# BRX.net
KiCad netlist of a schematic drawn in EAGLE
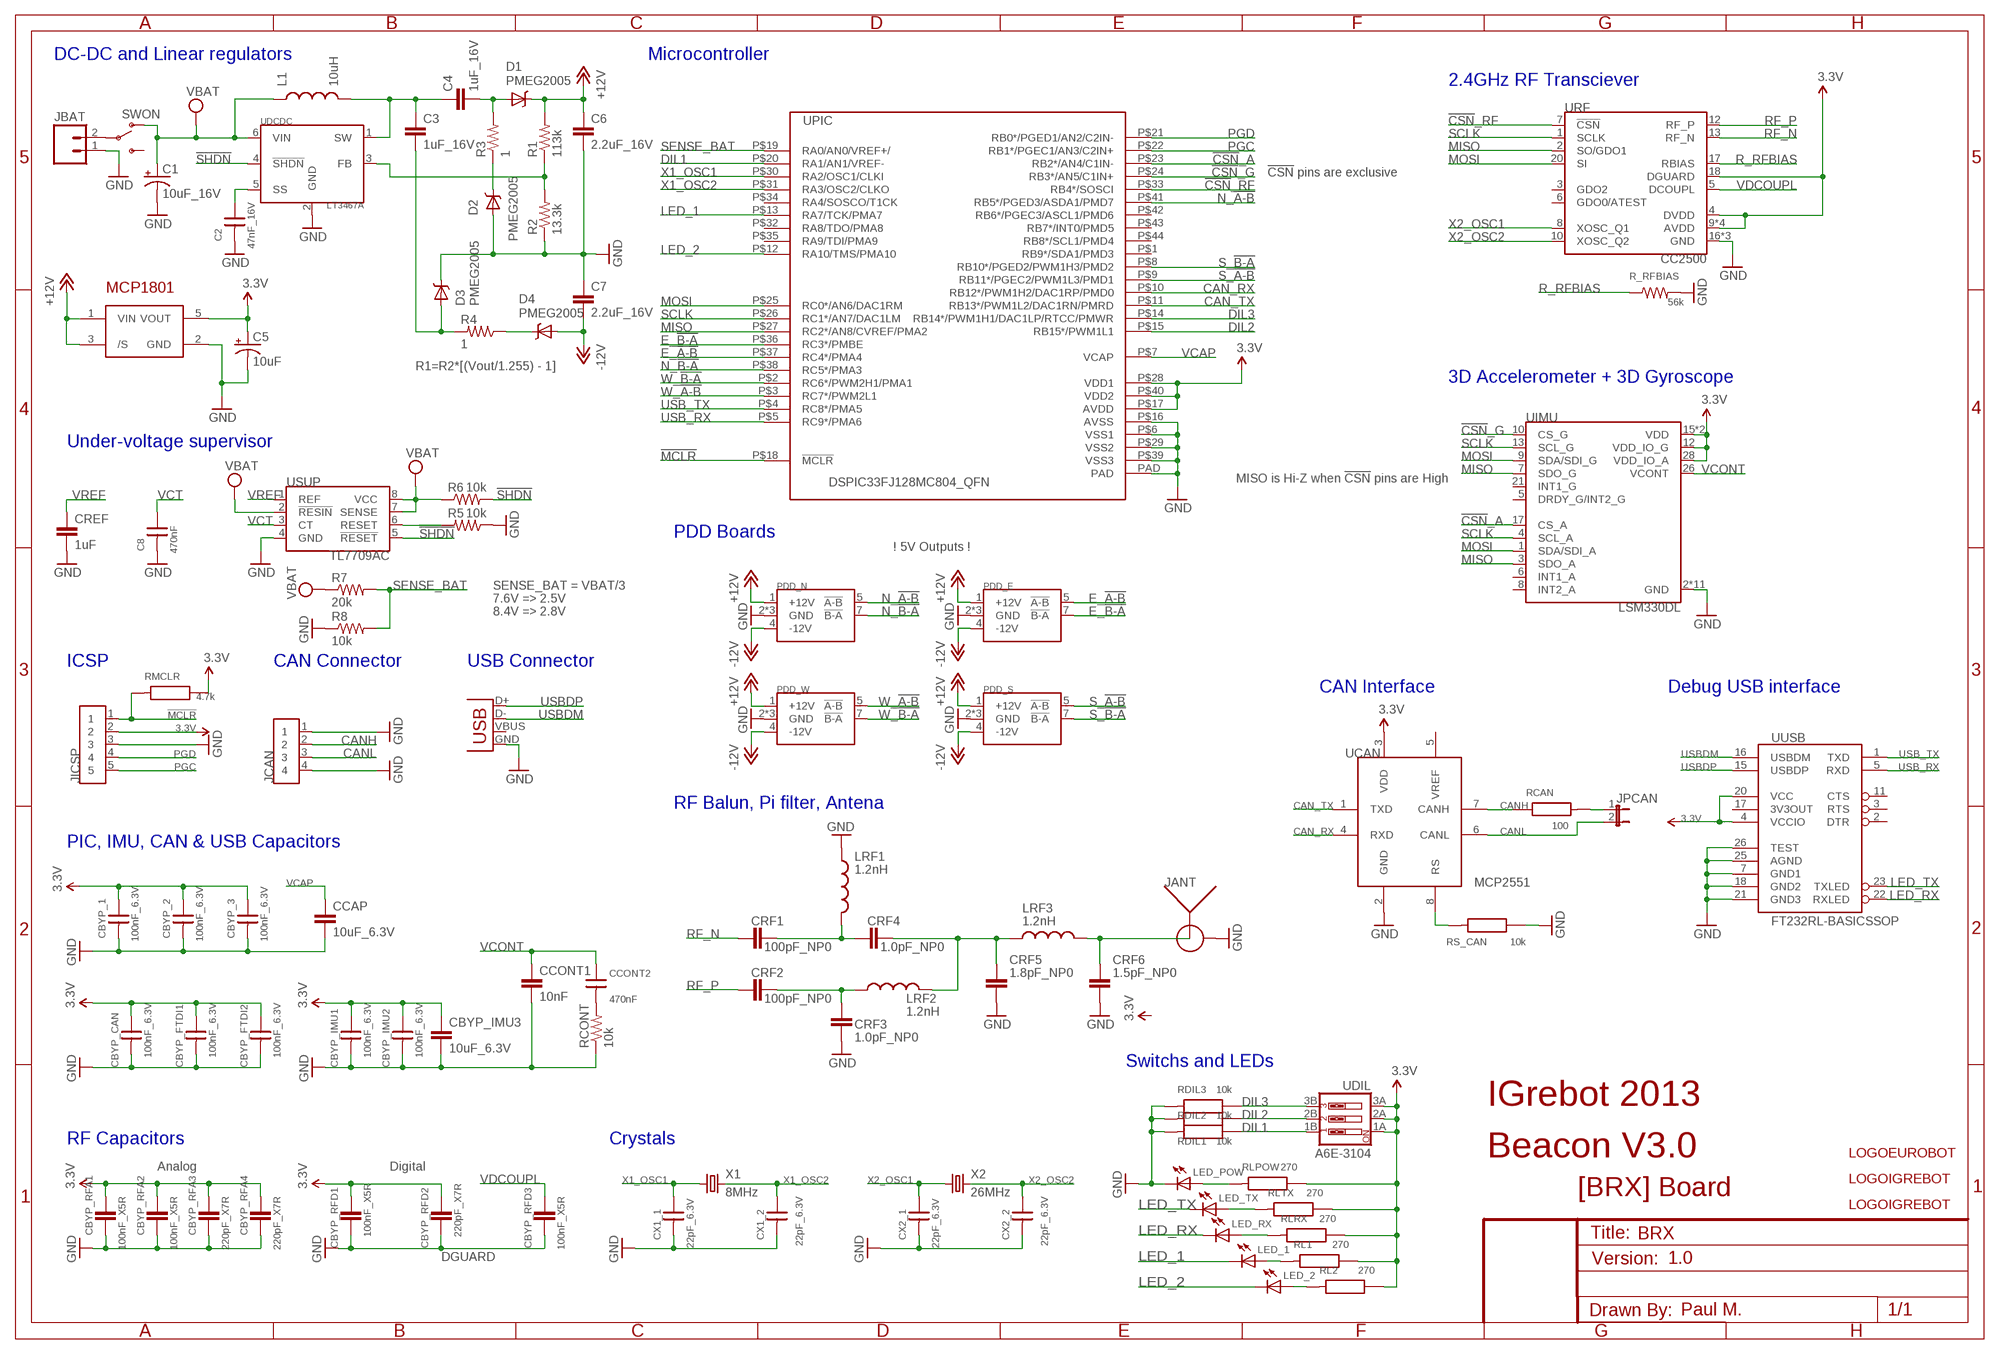
[diagram p0: schematic, sheet 1]

(export (version "E")
  (design (tool "Eeschema 10.0.6"))
  (components
    (comp (ref "C1")
      (value "10uF_16V")
      (footprint "eagle-import:PANASONIC_C")
      (libsource (lib "eagle-import") (part "CAP_POLC"))
    )
    (comp (ref "C2")
      (value "47nF_16V")
      (footprint "eagle-import:R0603")
      (libsource (lib "eagle-import") (part "C0603"))
    )
    (comp (ref "C3")
      (value "1uF_16V")
      (footprint "eagle-import:1210")
      (libsource (lib "eagle-import") (part "SparkFun-Passives_CAP1210"))
    )
    (comp (ref "C4")
      (value "1uF_16V")
      (footprint "eagle-import:1210")
      (libsource (lib "eagle-import") (part "SparkFun-Passives_CAP1210"))
    )
    (comp (ref "C5")
      (value "10uF")
      (footprint "eagle-import:PANASONIC_C")
      (libsource (lib "eagle-import") (part "CAP_POLC"))
    )
    (comp (ref "C6")
      (value "2.2uF_16V")
      (footprint "eagle-import:1210")
      (libsource (lib "eagle-import") (part "SparkFun-Passives_CAP1210"))
    )
    (comp (ref "C7")
      (value "2.2uF_16V")
      (footprint "eagle-import:1210")
      (libsource (lib "eagle-import") (part "SparkFun-Passives_CAP1210"))
    )
    (comp (ref "C8")
      (value "470nF")
      (footprint "eagle-import:R0603")
      (libsource (lib "eagle-import") (part "C0603"))
    )
    (comp (ref "CBYP_1")
      (value "100nF_6.3V")
      (footprint "eagle-import:R0603")
      (libsource (lib "eagle-import") (part "C0603"))
    )
    (comp (ref "CBYP_2")
      (value "100nF_6.3V")
      (footprint "eagle-import:R0603")
      (libsource (lib "eagle-import") (part "C0603"))
    )
    (comp (ref "CBYP_3")
      (value "100nF_6.3V")
      (footprint "eagle-import:R0603")
      (libsource (lib "eagle-import") (part "C0603"))
    )
    (comp (ref "CBYP_CAN")
      (value "100nF_6.3V")
      (footprint "eagle-import:R0603")
      (libsource (lib "eagle-import") (part "C0603"))
    )
    (comp (ref "CBYP_FTDI1")
      (value "100nF_6.3V")
      (footprint "eagle-import:R0603")
      (libsource (lib "eagle-import") (part "C0603"))
    )
    (comp (ref "CBYP_FTDI2")
      (value "100nF_6.3V")
      (footprint "eagle-import:R0603")
      (libsource (lib "eagle-import") (part "C0603"))
    )
    (comp (ref "CBYP_IMU1")
      (value "100nF_6.3V")
      (footprint "eagle-import:R0603")
      (libsource (lib "eagle-import") (part "C0603"))
    )
    (comp (ref "CBYP_IMU2")
      (value "100nF_6.3V")
      (footprint "eagle-import:R0603")
      (libsource (lib "eagle-import") (part "C0603"))
    )
    (comp (ref "CBYP_IMU3")
      (value "10uF_6.3V")
      (footprint "eagle-import:1206")
      (libsource (lib "eagle-import") (part "CAP1206"))
    )
    (comp (ref "CBYP_RFA1")
      (value "100nF_X5R")
      (footprint "eagle-import:0402-CAP")
      (libsource (lib "eagle-import") (part "SparkFun-Passives_CAP0402-CAP"))
    )
    (comp (ref "CBYP_RFA2")
      (value "100nF_X5R")
      (footprint "eagle-import:0402-CAP")
      (libsource (lib "eagle-import") (part "SparkFun-Passives_CAP0402-CAP"))
    )
    (comp (ref "CBYP_RFA3")
      (value "220pF_X7R")
      (footprint "eagle-import:0402-CAP")
      (libsource (lib "eagle-import") (part "SparkFun-Passives_CAP0402-CAP"))
    )
    (comp (ref "CBYP_RFA4")
      (value "220pF_X7R")
      (footprint "eagle-import:0402-CAP")
      (libsource (lib "eagle-import") (part "SparkFun-Passives_CAP0402-CAP"))
    )
    (comp (ref "CBYP_RFD1")
      (value "100nF_X5R")
      (footprint "eagle-import:0402-CAP")
      (libsource (lib "eagle-import") (part "SparkFun-Passives_CAP0402-CAP"))
    )
    (comp (ref "CBYP_RFD2")
      (value "220pF_X7R")
      (footprint "eagle-import:0402-CAP")
      (libsource (lib "eagle-import") (part "SparkFun-Passives_CAP0402-CAP"))
    )
    (comp (ref "CBYP_RFD3")
      (value "100nF_X5R")
      (footprint "eagle-import:0402-CAP")
      (libsource (lib "eagle-import") (part "SparkFun-Passives_CAP0402-CAP"))
    )
    (comp (ref "CCAP")
      (value "10uF_6.3V")
      (footprint "eagle-import:1206")
      (libsource (lib "eagle-import") (part "CAP1206"))
    )
    (comp (ref "CCONT1")
      (value "10nF")
      (footprint "eagle-import:1206")
      (libsource (lib "eagle-import") (part "CAP1206"))
    )
    (comp (ref "CCONT2")
      (value "470nF")
      (footprint "eagle-import:R0603")
      (libsource (lib "eagle-import") (part "C0603"))
    )
    (comp (ref "CREF")
      (value "1uF")
      (footprint "eagle-import:1210")
      (libsource (lib "eagle-import") (part "SparkFun-Passives_CAP1210"))
    )
    (comp (ref "CRF1")
      (value "100pF_NP0")
      (footprint "eagle-import:0402-CAP")
      (libsource (lib "eagle-import") (part "SparkFun-Passives_CAP0402-CAP"))
    )
    (comp (ref "CRF2")
      (value "100pF_NP0")
      (footprint "eagle-import:0402-CAP")
      (libsource (lib "eagle-import") (part "SparkFun-Passives_CAP0402-CAP"))
    )
    (comp (ref "CRF3")
      (value "1.0pF_NP0")
      (footprint "eagle-import:0402-CAP")
      (libsource (lib "eagle-import") (part "SparkFun-Passives_CAP0402-CAP"))
    )
    (comp (ref "CRF4")
      (value "1.0pF_NP0")
      (footprint "eagle-import:0402-CAP")
      (libsource (lib "eagle-import") (part "SparkFun-Passives_CAP0402-CAP"))
    )
    (comp (ref "CRF5")
      (value "1.8pF_NP0")
      (footprint "eagle-import:0402-CAP")
      (libsource (lib "eagle-import") (part "SparkFun-Passives_CAP0402-CAP"))
    )
    (comp (ref "CRF6")
      (value "1.5pF_NP0")
      (footprint "eagle-import:0402-CAP")
      (libsource (lib "eagle-import") (part "SparkFun-Passives_CAP0402-CAP"))
    )
    (comp (ref "CX1_1")
      (value "22pF_6.3V")
      (footprint "eagle-import:R0603")
      (libsource (lib "eagle-import") (part "C0603"))
    )
    (comp (ref "CX1_2")
      (value "22pF_6.3V")
      (footprint "eagle-import:R0603")
      (libsource (lib "eagle-import") (part "C0603"))
    )
    (comp (ref "CX2_1")
      (value "22pF_6.3V")
      (footprint "eagle-import:R0603")
      (libsource (lib "eagle-import") (part "C0603"))
    )
    (comp (ref "CX2_2")
      (value "22pF_6.3V")
      (footprint "eagle-import:R0603")
      (libsource (lib "eagle-import") (part "C0603"))
    )
    (comp (ref "D1")
      (value "PMEG2005")
      (footprint "eagle-import:SOD-523")
      (libsource (lib "eagle-import") (part "DIODE-SCHOTTKY"))
    )
    (comp (ref "D2")
      (value "PMEG2005")
      (footprint "eagle-import:SOD-523")
      (libsource (lib "eagle-import") (part "DIODE-SCHOTTKY"))
    )
    (comp (ref "D3")
      (value "PMEG2005")
      (footprint "eagle-import:SOD-523")
      (libsource (lib "eagle-import") (part "DIODE-SCHOTTKY"))
    )
    (comp (ref "D4")
      (value "PMEG2005")
      (footprint "eagle-import:SOD-523")
      (libsource (lib "eagle-import") (part "DIODE-SCHOTTKY"))
    )
    (comp (ref "JANT")
      (value "ENG_CD_1814400_C1")
      (footprint "eagle-import:SMA-PCB-ANGLE")
      (libsource (lib "eagle-import") (part "ENG_CD_1814400_C1"))
    )
    (comp (ref "JBAT")
      (value "M02JST-PTH-2")
      (footprint "eagle-import:JST-2-PTH")
      (libsource (lib "eagle-import") (part "M02JST-PTH-2"))
    )
    (comp (ref "JCAN")
      (value "SIL4")
      (footprint "eagle-import:CON4-2.54")
      (libsource (lib "eagle-import") (part "SIL4"))
    )
    (comp (ref "JICSP")
      (value "SIL5")
      (footprint "eagle-import:CON5-2.54")
      (libsource (lib "eagle-import") (part "SIL5"))
    )
    (comp (ref "JPCAN")
      (value "JUMPER-2PTH_LOCK")
      (footprint "eagle-import:1X02_LOCK")
      (libsource (lib "eagle-import") (part "JUMPER-2PTH_LOCK"))
    )
    (comp (ref "JUSB")
      (value "USBSMD")
      (footprint "eagle-import:USB-MINIB")
      (libsource (lib "eagle-import") (part "USBSMD"))
    )
    (comp (ref "L1")
      (value "10uH")
      (footprint "eagle-import:L-5X5")
      (libsource (lib "eagle-import") (part "MCSDC0503-221KU"))
    )
    (comp (ref "LED_1")
      (value "LED0603")
      (footprint "eagle-import:LED-0603")
      (libsource (lib "eagle-import") (part "LED0603"))
    )
    (comp (ref "LED_2")
      (value "LED0603")
      (footprint "eagle-import:LED-0603")
      (libsource (lib "eagle-import") (part "LED0603"))
    )
    (comp (ref "LED_POW")
      (value "LED0603")
      (footprint "eagle-import:LED-0603")
      (libsource (lib "eagle-import") (part "LED0603"))
    )
    (comp (ref "LED_RX")
      (value "LED0603")
      (footprint "eagle-import:LED-0603")
      (libsource (lib "eagle-import") (part "LED0603"))
    )
    (comp (ref "LED_TX")
      (value "LED0603")
      (footprint "eagle-import:LED-0603")
      (libsource (lib "eagle-import") (part "LED0603"))
    )
    (comp (ref "LRF1")
      (value "1.2nH")
      (footprint "eagle-import:C0402")
      (libsource (lib "eagle-import") (part "INDUCTOR0402"))
    )
    (comp (ref "LRF2")
      (value "1.2nH")
      (footprint "eagle-import:C0402")
      (libsource (lib "eagle-import") (part "INDUCTOR0402"))
    )
    (comp (ref "LRF3")
      (value "1.2nH")
      (footprint "eagle-import:C0402")
      (libsource (lib "eagle-import") (part "INDUCTOR0402"))
    )
    (comp (ref "PDD_E")
      (value "PDD_BOARD")
      (footprint "eagle-import:PDD_SOCKET")
      (libsource (lib "eagle-import") (part "PDD_BOARD"))
    )
    (comp (ref "PDD_N")
      (value "PDD_BOARD")
      (footprint "eagle-import:PDD_SOCKET")
      (libsource (lib "eagle-import") (part "PDD_BOARD"))
    )
    (comp (ref "PDD_S")
      (value "PDD_BOARD")
      (footprint "eagle-import:PDD_SOCKET")
      (libsource (lib "eagle-import") (part "PDD_BOARD"))
    )
    (comp (ref "PDD_W")
      (value "PDD_BOARD")
      (footprint "eagle-import:PDD_SOCKET")
      (libsource (lib "eagle-import") (part "PDD_BOARD"))
    )
    (comp (ref "R1")
      (value "113k")
      (footprint "eagle-import:0603-RES")
      (libsource (lib "eagle-import") (part "RESISTOR0603-RES"))
    )
    (comp (ref "R2")
      (value "13.3k")
      (footprint "eagle-import:0603-RES")
      (libsource (lib "eagle-import") (part "RESISTOR0603-RES"))
    )
    (comp (ref "R3")
      (value "1")
      (footprint "eagle-import:0603-RES")
      (libsource (lib "eagle-import") (part "RESISTOR0603-RES"))
    )
    (comp (ref "R4")
      (value "1")
      (footprint "eagle-import:0603-RES")
      (libsource (lib "eagle-import") (part "RESISTOR0603-RES"))
    )
    (comp (ref "R5")
      (value "10k")
      (footprint "eagle-import:0603-RES")
      (libsource (lib "eagle-import") (part "RESISTOR0603-RES"))
    )
    (comp (ref "R6")
      (value "10k")
      (footprint "eagle-import:0603-RES")
      (libsource (lib "eagle-import") (part "RESISTOR0603-RES"))
    )
    (comp (ref "R7")
      (value "20k")
      (footprint "eagle-import:0603-RES")
      (libsource (lib "eagle-import") (part "RESISTOR0603-RES"))
    )
    (comp (ref "R8")
      (value "10k")
      (footprint "eagle-import:0603-RES")
      (libsource (lib "eagle-import") (part "RESISTOR0603-RES"))
    )
    (comp (ref "RCAN")
      (value "100")
      (footprint "eagle-import:R0603")
      (libsource (lib "eagle-import") (part "R0603"))
    )
    (comp (ref "RCONT")
      (value "10k")
      (footprint "eagle-import:0603-RES")
      (libsource (lib "eagle-import") (part "RESISTOR0603-RES"))
    )
    (comp (ref "RDIL1")
      (value "10k")
      (footprint "eagle-import:R0603")
      (libsource (lib "eagle-import") (part "R0603"))
    )
    (comp (ref "RDIL2")
      (value "10k")
      (footprint "eagle-import:R0603")
      (libsource (lib "eagle-import") (part "R0603"))
    )
    (comp (ref "RDIL3")
      (value "10k")
      (footprint "eagle-import:R0603")
      (libsource (lib "eagle-import") (part "R0603"))
    )
    (comp (ref "RL1")
      (value "270")
      (footprint "eagle-import:R0603")
      (libsource (lib "eagle-import") (part "R0603"))
    )
    (comp (ref "RL2")
      (value "270")
      (footprint "eagle-import:R0603")
      (libsource (lib "eagle-import") (part "R0603"))
    )
    (comp (ref "RLPOW")
      (value "270")
      (footprint "eagle-import:R0603")
      (libsource (lib "eagle-import") (part "R0603"))
    )
    (comp (ref "RLRX")
      (value "270")
      (footprint "eagle-import:R0603")
      (libsource (lib "eagle-import") (part "R0603"))
    )
    (comp (ref "RLTX")
      (value "270")
      (footprint "eagle-import:R0603")
      (libsource (lib "eagle-import") (part "R0603"))
    )
    (comp (ref "RMCLR")
      (value "4.7k")
      (footprint "eagle-import:R0603")
      (libsource (lib "eagle-import") (part "R0603"))
    )
    (comp (ref "RS_CAN")
      (value "10k")
      (footprint "eagle-import:R0603")
      (libsource (lib "eagle-import") (part "R0603"))
    )
    (comp (ref "R_RFBIAS")
      (value "56k")
      (footprint "eagle-import:0402-RES")
      (libsource (lib "eagle-import") (part "RESISTOR0402-RES"))
    )
    (comp (ref "SWON")
      (value "SWITCH-SPDTPTH")
      (footprint "eagle-import:SWITCH-SPDT")
      (libsource (lib "eagle-import") (part "SWITCH-SPDTPTH"))
    )
    (comp (ref "U$3")
      (value "LOGOEUROBOT")
      (footprint "eagle-import:LOGO_EUROBOT_1")
      (libsource (lib "eagle-import") (part "LOGOEUROBOT"))
    )
    (comp (ref "U$5")
      (value "LOGOIGREBOT")
      (footprint "eagle-import:LOGO_IGREBOT")
      (libsource (lib "eagle-import") (part "LOGOIGREBOT"))
    )
    (comp (ref "U$9")
      (value "LOGOIGREBOT")
      (footprint "eagle-import:LOGO_IGREBOT")
      (libsource (lib "eagle-import") (part "LOGOIGREBOT"))
    )
    (comp (ref "UCAN")
      (value "MCP2551")
      (footprint "eagle-import:SO-08")
      (libsource (lib "eagle-import") (part "MCP2551"))
    )
    (comp (ref "UDCDC")
      (value "LT3467A")
      (footprint "eagle-import:TSOT-23")
      (libsource (lib "eagle-import") (part "LT3467A"))
    )
    (comp (ref "UDIL")
      (value "A6E-3104")
      (footprint "eagle-import:SW_DIP-3")
      (libsource (lib "eagle-import") (part "A6E-3104"))
    )
    (comp (ref "UIMU")
      (value "LSM330DL")
      (footprint "eagle-import:LLGA-28")
      (libsource (lib "eagle-import") (part "LSM330DL"))
    )
    (comp (ref "UPIC")
      (value "DSPIC33FJ128MC804_QFN")
      (footprint "eagle-import:QFN44-8X8")
      (libsource (lib "eagle-import") (part "DSPIC33FJ128MC804_QFN"))
    )
    (comp (ref "UREG")
      (value "MCP1801")
      (footprint "eagle-import:SOT23-5L")
      (libsource (lib "eagle-import") (part "MCP1801"))
    )
    (comp (ref "URF")
      (value "CC2500")
      (footprint "eagle-import:QFN20-0.5")
      (libsource (lib "eagle-import") (part "CC2500"))
    )
    (comp (ref "USUP")
      (value "TL7709AC")
      (footprint "eagle-import:SOIC8")
      (libsource (lib "eagle-import") (part "TL7709AC"))
    )
    (comp (ref "UUSB")
      (value "FT232RL-BASICSSOP")
      (footprint "eagle-import:SSOP28DB")
      (libsource (lib "eagle-import") (part "FT232RL-BASICSSOP"))
    )
    (comp (ref "X1")
      (value "8MHz")
      (footprint "eagle-import:XTAL_4.9-1.8")
      (libsource (lib "eagle-import") (part "XTAL4.8_1.8"))
    )
    (comp (ref "X2")
      (value "26MHz")
      (footprint "eagle-import:XTAL_4.9-1.8")
      (libsource (lib "eagle-import") (part "XTAL4.8_1.8"))
    )
  )
  (nets
    (net (code "1") (name "+12V") (class "Default")
      (node (ref "C6") (pin "1") (pinfunction "1_1") (pintype "passive"))
      (node (ref "D1") (pin "C") (pinfunction "C_C") (pintype "passive"))
      (node (ref "PDD_E") (pin "1") (pinfunction "+12V_1") (pintype "bidirectional"))
      (node (ref "PDD_N") (pin "1") (pinfunction "+12V_1") (pintype "bidirectional"))
      (node (ref "PDD_S") (pin "1") (pinfunction "+12V_1") (pintype "bidirectional"))
      (node (ref "PDD_W") (pin "1") (pinfunction "+12V_1") (pintype "bidirectional"))
      (node (ref "R1") (pin "2") (pinfunction "2_2") (pintype "passive"))
      (node (ref "UREG") (pin "1") (pinfunction "VIN_1") (pintype "bidirectional"))
      (node (ref "UREG") (pin "3") (pinfunction "/S_3") (pintype "bidirectional"))
    )
    (net (code "2") (name "-12V") (class "Default")
      (node (ref "C7") (pin "1") (pinfunction "1_1") (pintype "passive"))
      (node (ref "D4") (pin "A") (pinfunction "A_A") (pintype "passive"))
      (node (ref "PDD_E") (pin "4") (pinfunction "-12V_4") (pintype "bidirectional"))
      (node (ref "PDD_N") (pin "4") (pinfunction "-12V_4") (pintype "bidirectional"))
      (node (ref "PDD_S") (pin "4") (pinfunction "-12V_4") (pintype "bidirectional"))
      (node (ref "PDD_W") (pin "4") (pinfunction "-12V_4") (pintype "bidirectional"))
    )
    (net (code "3") (name "/CANH") (class "Default")
      (node (ref "JCAN") (pin "2") (pinfunction "2_2") (pintype "bidirectional"))
      (node (ref "RCAN") (pin "1") (pinfunction "1_1") (pintype "bidirectional"))
      (node (ref "UCAN") (pin "7") (pinfunction "CANH_7") (pintype "bidirectional"))
    )
    (net (code "4") (name "/CANL") (class "Default")
      (node (ref "JCAN") (pin "3") (pinfunction "3_3") (pintype "bidirectional"))
      (node (ref "JPCAN") (pin "2") (pinfunction "2_2") (pintype "passive"))
      (node (ref "UCAN") (pin "6") (pinfunction "CANL_6") (pintype "bidirectional"))
    )
    (net (code "5") (name "/CAN_RX") (class "Default")
      (node (ref "UCAN") (pin "4") (pinfunction "RXD_4") (pintype "bidirectional"))
      (node (ref "UPIC") (pin "P$10") (pinfunction "RB12*/PWM1H2/DAC1RP/PMD0_P$10") (pintype "bidirectional"))
    )
    (net (code "6") (name "/CAN_TX") (class "Default")
      (node (ref "UCAN") (pin "1") (pinfunction "TXD_1") (pintype "bidirectional"))
      (node (ref "UPIC") (pin "P$11") (pinfunction "RB13*/PWM1L2/DAC1RN/PMRD_P$11") (pintype "bidirectional"))
    )
    (net (code "7") (name "/DIL1") (class "Default")
      (node (ref "RDIL1") (pin "1") (pinfunction "1_1") (pintype "bidirectional"))
      (node (ref "UDIL") (pin "1B") (pinfunction "1B_1B") (pintype "passive"))
      (node (ref "UPIC") (pin "P$20") (pinfunction "RA1/AN1/VREF-_P$20") (pintype "bidirectional"))
    )
    (net (code "8") (name "/DIL2") (class "Default")
      (node (ref "RDIL2") (pin "1") (pinfunction "1_1") (pintype "bidirectional"))
      (node (ref "UDIL") (pin "2B") (pinfunction "2B_2B") (pintype "passive"))
      (node (ref "UPIC") (pin "P$15") (pinfunction "RB15*/PWM1L1_P$15") (pintype "bidirectional"))
    )
    (net (code "9") (name "/DIL3") (class "Default")
      (node (ref "RDIL3") (pin "1") (pinfunction "1_1") (pintype "bidirectional"))
      (node (ref "UDIL") (pin "3B") (pinfunction "3B_3B") (pintype "passive"))
      (node (ref "UPIC") (pin "P$14") (pinfunction "RB14*/PWM1H1/DAC1LP/RTCC/PMWR_P$14") (pintype "bidirectional"))
    )
    (net (code "10") (name "/E_~{A-B}") (class "Default")
      (node (ref "PDD_E") (pin "5") (pinfunction "~{A-B}_5") (pintype "bidirectional"))
      (node (ref "UPIC") (pin "P$37") (pinfunction "RC4*/PMA4_P$37") (pintype "bidirectional"))
    )
    (net (code "11") (name "/E_~{B-A}") (class "Default")
      (node (ref "PDD_E") (pin "7") (pinfunction "~{B-A}_7") (pintype "bidirectional"))
      (node (ref "UPIC") (pin "P$36") (pinfunction "RC3*/PMBE_P$36") (pintype "bidirectional"))
    )
    (net (code "12") (name "/LED_1") (class "Default")
      (node (ref "LED_1") (pin "C") (pinfunction "C_C") (pintype "passive"))
      (node (ref "UPIC") (pin "P$13") (pinfunction "RA7/TCK/PMA7_P$13") (pintype "bidirectional"))
    )
    (net (code "13") (name "/LED_2") (class "Default")
      (node (ref "LED_2") (pin "C") (pinfunction "C_C") (pintype "passive"))
      (node (ref "UPIC") (pin "P$12") (pinfunction "RA10/TMS/PMA10_P$12") (pintype "bidirectional"))
    )
    (net (code "14") (name "/LED_RX") (class "Default")
      (node (ref "LED_RX") (pin "C") (pinfunction "C_C") (pintype "passive"))
      (node (ref "UUSB") (pin "22") (pinfunction "RXLED_22") (pintype "bidirectional"))
    )
    (net (code "15") (name "/LED_TX") (class "Default")
      (node (ref "LED_TX") (pin "C") (pinfunction "C_C") (pintype "passive"))
      (node (ref "UUSB") (pin "23") (pinfunction "TXLED_23") (pintype "bidirectional"))
    )
    (net (code "16") (name "/MISO") (class "Default")
      (node (ref "UIMU") (pin "3") (pinfunction "SDO_A_3") (pintype "bidirectional"))
      (node (ref "UIMU") (pin "7") (pinfunction "SDO_G_7") (pintype "bidirectional"))
      (node (ref "UPIC") (pin "P$27") (pinfunction "RC2*/AN8/CVREF/PMA2_P$27") (pintype "bidirectional"))
      (node (ref "URF") (pin "2") (pinfunction "SO/GDO1_2") (pintype "bidirectional"))
    )
    (net (code "17") (name "/MOSI") (class "Default")
      (node (ref "UIMU") (pin "1") (pinfunction "SDA/SDI_A_1") (pintype "bidirectional"))
      (node (ref "UIMU") (pin "9") (pinfunction "SDA/SDI_G_9") (pintype "bidirectional"))
      (node (ref "UPIC") (pin "P$25") (pinfunction "RC0*/AN6/DAC1RM_P$25") (pintype "bidirectional"))
      (node (ref "URF") (pin "20") (pinfunction "SI_20") (pintype "bidirectional"))
    )
    (net (code "18") (name "/N_~{A-B}") (class "Default")
      (node (ref "PDD_N") (pin "5") (pinfunction "~{A-B}_5") (pintype "bidirectional"))
      (node (ref "UPIC") (pin "P$41") (pinfunction "RB5*/PGED3/ASDA1/PMD7_P$41") (pintype "bidirectional"))
    )
    (net (code "19") (name "/N_~{B-A}") (class "Default")
      (node (ref "PDD_N") (pin "7") (pinfunction "~{B-A}_7") (pintype "bidirectional"))
      (node (ref "UPIC") (pin "P$38") (pinfunction "RC5*/PMA3_P$38") (pintype "bidirectional"))
    )
    (net (code "20") (name "/PGC") (class "Default")
      (node (ref "JICSP") (pin "5") (pinfunction "5_5") (pintype "bidirectional"))
      (node (ref "UPIC") (pin "P$22") (pinfunction "RB1*/PGEC1/AN3/C2IN+_P$22") (pintype "bidirectional"))
    )
    (net (code "21") (name "/PGD") (class "Default")
      (node (ref "JICSP") (pin "4") (pinfunction "4_4") (pintype "bidirectional"))
      (node (ref "UPIC") (pin "P$21") (pinfunction "RB0*/PGED1/AN2/C2IN-_P$21") (pintype "bidirectional"))
    )
    (net (code "22") (name "/RF_N") (class "Default")
      (node (ref "CRF1") (pin "1") (pinfunction "1_1") (pintype "passive"))
      (node (ref "URF") (pin "13") (pinfunction "RF_N_13") (pintype "bidirectional"))
    )
    (net (code "23") (name "/RF_P") (class "Default")
      (node (ref "CRF2") (pin "1") (pinfunction "1_1") (pintype "passive"))
      (node (ref "URF") (pin "12") (pinfunction "RF_P_12") (pintype "bidirectional"))
    )
    (net (code "24") (name "/R_RFBIAS") (class "Default")
      (node (ref "R_RFBIAS") (pin "1") (pinfunction "1_1") (pintype "passive"))
      (node (ref "URF") (pin "17") (pinfunction "RBIAS_17") (pintype "bidirectional"))
    )
    (net (code "25") (name "/SCLK") (class "Default")
      (node (ref "UIMU") (pin "13") (pinfunction "SCL_G_13") (pintype "bidirectional"))
      (node (ref "UIMU") (pin "4") (pinfunction "SCL_A_4") (pintype "bidirectional"))
      (node (ref "UPIC") (pin "P$26") (pinfunction "RC1*/AN7/DAC1LM_P$26") (pintype "bidirectional"))
      (node (ref "URF") (pin "1") (pinfunction "SCLK_1") (pintype "bidirectional"))
    )
    (net (code "26") (name "/SENSE_BAT") (class "Default")
      (node (ref "R7") (pin "2") (pinfunction "2_2") (pintype "passive"))
      (node (ref "R8") (pin "2") (pinfunction "2_2") (pintype "passive"))
      (node (ref "UPIC") (pin "P$19") (pinfunction "RA0/AN0/VREF+/_P$19") (pintype "bidirectional"))
    )
    (net (code "27") (name "/S_~{A-B}") (class "Default")
      (node (ref "PDD_S") (pin "5") (pinfunction "~{A-B}_5") (pintype "bidirectional"))
      (node (ref "UPIC") (pin "P$9") (pinfunction "RB11*/PGEC2/PWM1L3/PMD1_P$9") (pintype "bidirectional"))
    )
    (net (code "28") (name "/S_~{B-A}") (class "Default")
      (node (ref "PDD_S") (pin "7") (pinfunction "~{B-A}_7") (pintype "bidirectional"))
      (node (ref "UPIC") (pin "P$8") (pinfunction "RB10*/PGED2/PWM1H3/PMD2_P$8") (pintype "bidirectional"))
    )
    (net (code "29") (name "/USBDM") (class "Default")
      (node (ref "JUSB") (pin "D-") (pinfunction "D-_D-") (pintype "bidirectional"))
      (node (ref "UUSB") (pin "16") (pinfunction "USBDM_16") (pintype "bidirectional"))
    )
    (net (code "30") (name "/USBDP") (class "Default")
      (node (ref "JUSB") (pin "D+") (pinfunction "D+_D+") (pintype "bidirectional"))
      (node (ref "UUSB") (pin "15") (pinfunction "USBDP_15") (pintype "bidirectional"))
    )
    (net (code "31") (name "/USB_RX") (class "Default")
      (node (ref "UPIC") (pin "P$5") (pinfunction "RC9*/PMA6_P$5") (pintype "bidirectional"))
      (node (ref "UUSB") (pin "5") (pinfunction "RXD_5") (pintype "input"))
    )
    (net (code "32") (name "/USB_TX") (class "Default")
      (node (ref "UPIC") (pin "P$4") (pinfunction "RC8*/PMA5_P$4") (pintype "bidirectional"))
      (node (ref "UUSB") (pin "1") (pinfunction "TXD_1") (pintype "output"))
    )
    (net (code "33") (name "/VCAP") (class "Default")
      (node (ref "CCAP") (pin "1") (pinfunction "1_1") (pintype "passive"))
      (node (ref "UPIC") (pin "P$7") (pinfunction "VCAP_P$7") (pintype "bidirectional"))
    )
    (net (code "34") (name "/VCONT") (class "Default")
      (node (ref "CCONT1") (pin "1") (pinfunction "1_1") (pintype "passive"))
      (node (ref "CCONT2") (pin "1") (pinfunction "1_1") (pintype "bidirectional"))
      (node (ref "UIMU") (pin "26") (pinfunction "VCONT_26") (pintype "bidirectional"))
    )
    (net (code "35") (name "/VCT") (class "Default")
      (node (ref "C8") (pin "1") (pinfunction "1_1") (pintype "bidirectional"))
      (node (ref "USUP") (pin "3") (pinfunction "CT_3") (pintype "bidirectional"))
    )
    (net (code "36") (name "/VDCOUPL") (class "Default")
      (node (ref "CBYP_RFD3") (pin "2") (pinfunction "2_2") (pintype "passive"))
      (node (ref "URF") (pin "5") (pinfunction "DCOUPL_5") (pintype "bidirectional"))
    )
    (net (code "37") (name "/VREF") (class "Default")
      (node (ref "CREF") (pin "2") (pinfunction "2_2") (pintype "passive"))
      (node (ref "USUP") (pin "1") (pinfunction "REF_1") (pintype "bidirectional"))
    )
    (net (code "38") (name "/W_~{A-B}") (class "Default")
      (node (ref "PDD_W") (pin "5") (pinfunction "~{A-B}_5") (pintype "bidirectional"))
      (node (ref "UPIC") (pin "P$3") (pinfunction "RC7*/PWM2L1_P$3") (pintype "bidirectional"))
    )
    (net (code "39") (name "/W_~{B-A}") (class "Default")
      (node (ref "PDD_W") (pin "7") (pinfunction "~{B-A}_7") (pintype "bidirectional"))
      (node (ref "UPIC") (pin "P$2") (pinfunction "RC6*/PWM2H1/PMA1_P$2") (pintype "bidirectional"))
    )
    (net (code "40") (name "/X1_OSC1") (class "Default")
      (node (ref "CX1_1") (pin "1") (pinfunction "1_1") (pintype "bidirectional"))
      (node (ref "UPIC") (pin "P$30") (pinfunction "RA2/OSC1/CLKI_P$30") (pintype "bidirectional"))
      (node (ref "X1") (pin "P$1") (pinfunction "1_P$1") (pintype "passive"))
    )
    (net (code "41") (name "/X1_OSC2") (class "Default")
      (node (ref "CX1_2") (pin "1") (pinfunction "1_1") (pintype "bidirectional"))
      (node (ref "UPIC") (pin "P$31") (pinfunction "RA3/OSC2/CLKO_P$31") (pintype "bidirectional"))
      (node (ref "X1") (pin "P$2") (pinfunction "2_P$2") (pintype "passive"))
    )
    (net (code "42") (name "/X2_OSC1") (class "Default")
      (node (ref "CX2_1") (pin "1") (pinfunction "1_1") (pintype "bidirectional"))
      (node (ref "URF") (pin "8") (pinfunction "XOSC_Q1_8") (pintype "bidirectional"))
      (node (ref "X2") (pin "P$1") (pinfunction "1_P$1") (pintype "passive"))
    )
    (net (code "43") (name "/X2_OSC2") (class "Default")
      (node (ref "CX2_2") (pin "1") (pinfunction "1_1") (pintype "bidirectional"))
      (node (ref "URF") (pin "10") (pinfunction "XOSC_Q2_10") (pintype "bidirectional"))
      (node (ref "X2") (pin "P$2") (pinfunction "2_P$2") (pintype "passive"))
    )
    (net (code "44") (name "/~{CSN}_A") (class "Default")
      (node (ref "UIMU") (pin "17") (pinfunction "CS_A_17") (pintype "bidirectional"))
      (node (ref "UPIC") (pin "P$23") (pinfunction "RB2*/AN4/C1IN-_P$23") (pintype "bidirectional"))
    )
    (net (code "45") (name "/~{CSN}_G") (class "Default")
      (node (ref "UIMU") (pin "10") (pinfunction "CS_G_10") (pintype "bidirectional"))
      (node (ref "UPIC") (pin "P$24") (pinfunction "RB3*/AN5/C1IN+_P$24") (pintype "bidirectional"))
    )
    (net (code "46") (name "/~{CSN}_RF") (class "Default")
      (node (ref "UPIC") (pin "P$33") (pinfunction "RB4*/SOSCI_P$33") (pintype "bidirectional"))
      (node (ref "URF") (pin "7") (pinfunction "~{CSN}_7") (pintype "bidirectional"))
    )
    (net (code "47") (name "/~{MCLR}") (class "Default")
      (node (ref "JICSP") (pin "1") (pinfunction "1_1") (pintype "bidirectional"))
      (node (ref "RMCLR") (pin "2") (pinfunction "2_2") (pintype "bidirectional"))
      (node (ref "UPIC") (pin "P$18") (pinfunction "~{MCLR}_P$18") (pintype "bidirectional"))
    )
    (net (code "48") (name "/~{SHDN}") (class "Default")
      (node (ref "R6") (pin "2") (pinfunction "2_2") (pintype "passive"))
      (node (ref "UDCDC") (pin "4") (pinfunction "~{SHDN}_4") (pintype "bidirectional"))
      (node (ref "USUP") (pin "5") (pinfunction "~{RESET}_5") (pintype "bidirectional"))
    )
    (net (code "49") (name "3.3V") (class "Default")
      (node (ref "C5") (pin "+") (pinfunction "+_+") (pintype "passive"))
      (node (ref "CBYP_1") (pin "1") (pinfunction "1_1") (pintype "bidirectional"))
      (node (ref "CBYP_2") (pin "1") (pinfunction "1_1") (pintype "bidirectional"))
      (node (ref "CBYP_3") (pin "1") (pinfunction "1_1") (pintype "bidirectional"))
      (node (ref "CBYP_CAN") (pin "1") (pinfunction "1_1") (pintype "bidirectional"))
      (node (ref "CBYP_FTDI1") (pin "1") (pinfunction "1_1") (pintype "bidirectional"))
      (node (ref "CBYP_FTDI2") (pin "1") (pinfunction "1_1") (pintype "bidirectional"))
      (node (ref "CBYP_IMU1") (pin "1") (pinfunction "1_1") (pintype "bidirectional"))
      (node (ref "CBYP_IMU2") (pin "1") (pinfunction "1_1") (pintype "bidirectional"))
      (node (ref "CBYP_IMU3") (pin "1") (pinfunction "1_1") (pintype "passive"))
      (node (ref "CBYP_RFA1") (pin "2") (pinfunction "2_2") (pintype "passive"))
      (node (ref "CBYP_RFA2") (pin "2") (pinfunction "2_2") (pintype "passive"))
      (node (ref "CBYP_RFA3") (pin "2") (pinfunction "2_2") (pintype "passive"))
      (node (ref "CBYP_RFA4") (pin "2") (pinfunction "2_2") (pintype "passive"))
      (node (ref "CBYP_RFD1") (pin "2") (pinfunction "2_2") (pintype "passive"))
      (node (ref "CBYP_RFD2") (pin "2") (pinfunction "2_2") (pintype "passive"))
      (node (ref "JICSP") (pin "2") (pinfunction "2_2") (pintype "bidirectional"))
      (node (ref "RL1") (pin "1") (pinfunction "1_1") (pintype "bidirectional"))
      (node (ref "RL2") (pin "1") (pinfunction "1_1") (pintype "bidirectional"))
      (node (ref "RLPOW") (pin "1") (pinfunction "1_1") (pintype "bidirectional"))
      (node (ref "RLRX") (pin "1") (pinfunction "1_1") (pintype "bidirectional"))
      (node (ref "RLTX") (pin "1") (pinfunction "1_1") (pintype "bidirectional"))
      (node (ref "RMCLR") (pin "1") (pinfunction "1_1") (pintype "bidirectional"))
      (node (ref "UCAN") (pin "3") (pinfunction "VDD_3") (pintype "bidirectional"))
      (node (ref "UDIL") (pin "1A") (pinfunction "1A_1A") (pintype "passive"))
      (node (ref "UDIL") (pin "2A") (pinfunction "2A_2A") (pintype "passive"))
      (node (ref "UDIL") (pin "3A") (pinfunction "3A_3A") (pintype "passive"))
      (node (ref "UIMU") (pin "12") (pinfunction "VDD_IO_G_12") (pintype "bidirectional"))
      (node (ref "UIMU") (pin "15") (pinfunction "VDD_15") (pintype "bidirectional"))
      (node (ref "UIMU") (pin "22") (pinfunction "VDD_22") (pintype "bidirectional"))
      (node (ref "UIMU") (pin "28") (pinfunction "VDD_IO_A_28") (pintype "bidirectional"))
      (node (ref "UPIC") (pin "P$17") (pinfunction "AVDD_P$17") (pintype "bidirectional"))
      (node (ref "UPIC") (pin "P$28") (pinfunction "VDD1_P$28") (pintype "bidirectional"))
      (node (ref "UPIC") (pin "P$40") (pinfunction "VDD2_P$40") (pintype "bidirectional"))
      (node (ref "UREG") (pin "5") (pinfunction "VOUT_5") (pintype "bidirectional"))
      (node (ref "URF") (pin "11") (pinfunction "AVDD_11") (pintype "bidirectional"))
      (node (ref "URF") (pin "14") (pinfunction "AVDD_14") (pintype "bidirectional"))
      (node (ref "URF") (pin "15") (pinfunction "AVDD_15") (pintype "bidirectional"))
      (node (ref "URF") (pin "18") (pinfunction "DGUARD_18") (pintype "bidirectional"))
      (node (ref "URF") (pin "4") (pinfunction "DVDD_4") (pintype "bidirectional"))
      (node (ref "URF") (pin "9") (pinfunction "AVDD_9") (pintype "bidirectional"))
      (node (ref "UUSB") (pin "20") (pinfunction "VCC_20") (pintype "power_in"))
      (node (ref "UUSB") (pin "4") (pinfunction "VCCIO_4") (pintype "power_in"))
    )
    (net (code "50") (name "GND") (class "Default")
      (node (ref "C1") (pin "-") (pinfunction "-_-") (pintype "passive"))
      (node (ref "C2") (pin "2") (pinfunction "2_2") (pintype "bidirectional"))
      (node (ref "C5") (pin "-") (pinfunction "-_-") (pintype "passive"))
      (node (ref "C6") (pin "2") (pinfunction "2_2") (pintype "passive"))
      (node (ref "C7") (pin "2") (pinfunction "2_2") (pintype "passive"))
      (node (ref "C8") (pin "2") (pinfunction "2_2") (pintype "bidirectional"))
      (node (ref "CBYP_1") (pin "2") (pinfunction "2_2") (pintype "bidirectional"))
      (node (ref "CBYP_2") (pin "2") (pinfunction "2_2") (pintype "bidirectional"))
      (node (ref "CBYP_3") (pin "2") (pinfunction "2_2") (pintype "bidirectional"))
      (node (ref "CBYP_CAN") (pin "2") (pinfunction "2_2") (pintype "bidirectional"))
      (node (ref "CBYP_FTDI1") (pin "2") (pinfunction "2_2") (pintype "bidirectional"))
      (node (ref "CBYP_FTDI2") (pin "2") (pinfunction "2_2") (pintype "bidirectional"))
      (node (ref "CBYP_IMU1") (pin "2") (pinfunction "2_2") (pintype "bidirectional"))
      (node (ref "CBYP_IMU2") (pin "2") (pinfunction "2_2") (pintype "bidirectional"))
      (node (ref "CBYP_IMU3") (pin "2") (pinfunction "2_2") (pintype "passive"))
      (node (ref "CBYP_RFA1") (pin "1") (pinfunction "1_1") (pintype "passive"))
      (node (ref "CBYP_RFA2") (pin "1") (pinfunction "1_1") (pintype "passive"))
      (node (ref "CBYP_RFA3") (pin "1") (pinfunction "1_1") (pintype "passive"))
      (node (ref "CBYP_RFA4") (pin "1") (pinfunction "1_1") (pintype "passive"))
      (node (ref "CBYP_RFD1") (pin "1") (pinfunction "1_1") (pintype "passive"))
      (node (ref "CBYP_RFD2") (pin "1") (pinfunction "1_1") (pintype "passive"))
      (node (ref "CBYP_RFD3") (pin "1") (pinfunction "1_1") (pintype "passive"))
      (node (ref "CCAP") (pin "2") (pinfunction "2_2") (pintype "passive"))
      (node (ref "CCONT1") (pin "2") (pinfunction "2_2") (pintype "passive"))
      (node (ref "CREF") (pin "1") (pinfunction "1_1") (pintype "passive"))
      (node (ref "CRF3") (pin "1") (pinfunction "1_1") (pintype "passive"))
      (node (ref "CRF5") (pin "1") (pinfunction "1_1") (pintype "passive"))
      (node (ref "CRF6") (pin "1") (pinfunction "1_1") (pintype "passive"))
      (node (ref "CX1_1") (pin "2") (pinfunction "2_2") (pintype "bidirectional"))
      (node (ref "CX1_2") (pin "2") (pinfunction "2_2") (pintype "bidirectional"))
      (node (ref "CX2_1") (pin "2") (pinfunction "2_2") (pintype "bidirectional"))
      (node (ref "CX2_2") (pin "2") (pinfunction "2_2") (pintype "bidirectional"))
      (node (ref "D2") (pin "A") (pinfunction "A_A") (pintype "passive"))
      (node (ref "D3") (pin "C") (pinfunction "C_C") (pintype "passive"))
      (node (ref "JANT") (pin "B1") (pinfunction "B_B1") (pintype "bidirectional"))
      (node (ref "JANT") (pin "B2") (pinfunction "B_B2") (pintype "bidirectional"))
      (node (ref "JANT") (pin "B3") (pinfunction "B_B3") (pintype "bidirectional"))
      (node (ref "JANT") (pin "B4") (pinfunction "B_B4") (pintype "bidirectional"))
      (node (ref "JBAT") (pin "1") (pinfunction "1_1") (pintype "passive"))
      (node (ref "JCAN") (pin "1") (pinfunction "1_1") (pintype "bidirectional"))
      (node (ref "JCAN") (pin "4") (pinfunction "4_4") (pintype "bidirectional"))
      (node (ref "JICSP") (pin "3") (pinfunction "3_3") (pintype "bidirectional"))
      (node (ref "JUSB") (pin "GND") (pinfunction "GND_GND") (pintype "bidirectional"))
      (node (ref "LED_POW") (pin "C") (pinfunction "C_C") (pintype "passive"))
      (node (ref "LRF1") (pin "1") (pinfunction "1_1") (pintype "passive"))
      (node (ref "PDD_E") (pin "2") (pinfunction "GND_2") (pintype "bidirectional"))
      (node (ref "PDD_E") (pin "3") (pinfunction "GND_3") (pintype "bidirectional"))
      (node (ref "PDD_E") (pin "6") (pinfunction "GND_6") (pintype "bidirectional"))
      (node (ref "PDD_N") (pin "2") (pinfunction "GND_2") (pintype "bidirectional"))
      (node (ref "PDD_N") (pin "3") (pinfunction "GND_3") (pintype "bidirectional"))
      (node (ref "PDD_N") (pin "6") (pinfunction "GND_6") (pintype "bidirectional"))
      (node (ref "PDD_S") (pin "2") (pinfunction "GND_2") (pintype "bidirectional"))
      (node (ref "PDD_S") (pin "3") (pinfunction "GND_3") (pintype "bidirectional"))
      (node (ref "PDD_S") (pin "6") (pinfunction "GND_6") (pintype "bidirectional"))
      (node (ref "PDD_W") (pin "2") (pinfunction "GND_2") (pintype "bidirectional"))
      (node (ref "PDD_W") (pin "3") (pinfunction "GND_3") (pintype "bidirectional"))
      (node (ref "PDD_W") (pin "6") (pinfunction "GND_6") (pintype "bidirectional"))
      (node (ref "R2") (pin "1") (pinfunction "1_1") (pintype "passive"))
      (node (ref "R5") (pin "1") (pinfunction "1_1") (pintype "passive"))
      (node (ref "R8") (pin "1") (pinfunction "1_1") (pintype "passive"))
      (node (ref "RCONT") (pin "1") (pinfunction "1_1") (pintype "passive"))
      (node (ref "RDIL1") (pin "2") (pinfunction "2_2") (pintype "bidirectional"))
      (node (ref "RDIL2") (pin "2") (pinfunction "2_2") (pintype "bidirectional"))
      (node (ref "RDIL3") (pin "2") (pinfunction "2_2") (pintype "bidirectional"))
      (node (ref "RS_CAN") (pin "1") (pinfunction "1_1") (pintype "bidirectional"))
      (node (ref "R_RFBIAS") (pin "2") (pinfunction "2_2") (pintype "passive"))
      (node (ref "UCAN") (pin "2") (pinfunction "GND_2") (pintype "bidirectional"))
      (node (ref "UDCDC") (pin "2") (pinfunction "GND_2") (pintype "bidirectional"))
      (node (ref "UIMU") (pin "11") (pinfunction "GND_11") (pintype "bidirectional"))
      (node (ref "UIMU") (pin "14") (pinfunction "GND_14") (pintype "bidirectional"))
      (node (ref "UIMU") (pin "16") (pinfunction "GND_16") (pintype "bidirectional"))
      (node (ref "UIMU") (pin "18") (pinfunction "GND_18") (pintype "bidirectional"))
      (node (ref "UIMU") (pin "19") (pinfunction "GND_19") (pintype "bidirectional"))
      (node (ref "UIMU") (pin "2") (pinfunction "GND_2") (pintype "bidirectional"))
      (node (ref "UIMU") (pin "20") (pinfunction "GND_20") (pintype "bidirectional"))
      (node (ref "UIMU") (pin "23") (pinfunction "GND_23") (pintype "bidirectional"))
      (node (ref "UIMU") (pin "24") (pinfunction "GND_24") (pintype "bidirectional"))
      (node (ref "UIMU") (pin "25") (pinfunction "GND_25") (pintype "bidirectional"))
      (node (ref "UIMU") (pin "27") (pinfunction "GND_27") (pintype "bidirectional"))
      (node (ref "UPIC") (pin "P$16") (pinfunction "AVSS_P$16") (pintype "bidirectional"))
      (node (ref "UPIC") (pin "P$29") (pinfunction "VSS2_P$29") (pintype "bidirectional"))
      (node (ref "UPIC") (pin "P$39") (pinfunction "VSS3_P$39") (pintype "bidirectional"))
      (node (ref "UPIC") (pin "P$6") (pinfunction "VSS1_P$6") (pintype "bidirectional"))
      (node (ref "UPIC") (pin "PAD") (pinfunction "PAD_PAD") (pintype "bidirectional"))
      (node (ref "UREG") (pin "2") (pinfunction "GND_2") (pintype "bidirectional"))
      (node (ref "URF") (pin "16") (pinfunction "GND_16") (pintype "bidirectional"))
      (node (ref "URF") (pin "19") (pinfunction "GND_19") (pintype "bidirectional"))
      (node (ref "URF") (pin "PAD") (pinfunction "GND_PAD") (pintype "bidirectional"))
      (node (ref "USUP") (pin "4") (pinfunction "GND_4") (pintype "bidirectional"))
      (node (ref "UUSB") (pin "18") (pinfunction "GND2_18") (pintype "power_in"))
      (node (ref "UUSB") (pin "21") (pinfunction "GND3_21") (pintype "power_in"))
      (node (ref "UUSB") (pin "25") (pinfunction "AGND_25") (pintype "power_in"))
      (node (ref "UUSB") (pin "26") (pinfunction "TEST_26") (pintype "input"))
      (node (ref "UUSB") (pin "7") (pinfunction "GND1_7") (pintype "power_in"))
    )
    (net (code "51") (name "Net-(C3-Pad2)") (class "Default")
      (node (ref "C3") (pin "2") (pinfunction "2_2") (pintype "passive"))
      (node (ref "D3") (pin "A") (pinfunction "A_A") (pintype "passive"))
      (node (ref "R4") (pin "2") (pinfunction "2_2") (pintype "passive"))
    )
    (net (code "52") (name "Net-(C4-Pad2)") (class "Default")
      (node (ref "C4") (pin "2") (pinfunction "2_2") (pintype "passive"))
      (node (ref "D1") (pin "A") (pinfunction "A_A") (pintype "passive"))
      (node (ref "R3") (pin "2") (pinfunction "2_2") (pintype "passive"))
    )
    (net (code "53") (name "Net-(CCONT2-Pad2)") (class "Default")
      (node (ref "CCONT2") (pin "2") (pinfunction "2_2") (pintype "bidirectional"))
      (node (ref "RCONT") (pin "2") (pinfunction "2_2") (pintype "passive"))
    )
    (net (code "54") (name "Net-(CRF1-Pad2)") (class "Default")
      (node (ref "CRF1") (pin "2") (pinfunction "2_2") (pintype "passive"))
      (node (ref "CRF4") (pin "2") (pinfunction "2_2") (pintype "passive"))
      (node (ref "LRF1") (pin "2") (pinfunction "2_2") (pintype "passive"))
    )
    (net (code "55") (name "Net-(CRF2-Pad2)") (class "Default")
      (node (ref "CRF2") (pin "2") (pinfunction "2_2") (pintype "passive"))
      (node (ref "CRF3") (pin "2") (pinfunction "2_2") (pintype "passive"))
      (node (ref "LRF2") (pin "1") (pinfunction "1_1") (pintype "passive"))
    )
    (net (code "56") (name "Net-(CRF4-Pad1)") (class "Default")
      (node (ref "CRF4") (pin "1") (pinfunction "1_1") (pintype "passive"))
      (node (ref "CRF5") (pin "2") (pinfunction "2_2") (pintype "passive"))
      (node (ref "LRF2") (pin "2") (pinfunction "2_2") (pintype "passive"))
      (node (ref "LRF3") (pin "1") (pinfunction "1_1") (pintype "passive"))
    )
    (net (code "57") (name "Net-(CRF6-Pad2)") (class "Default")
      (node (ref "CRF6") (pin "2") (pinfunction "2_2") (pintype "passive"))
      (node (ref "JANT") (pin "A") (pinfunction "A_A") (pintype "bidirectional"))
      (node (ref "LRF3") (pin "2") (pinfunction "2_2") (pintype "passive"))
    )
    (net (code "58") (name "Net-(D2-PadC)") (class "Default")
      (node (ref "D2") (pin "C") (pinfunction "C_C") (pintype "passive"))
      (node (ref "R3") (pin "1") (pinfunction "1_1") (pintype "passive"))
    )
    (net (code "59") (name "Net-(D4-PadC)") (class "Default")
      (node (ref "D4") (pin "C") (pinfunction "C_C") (pintype "passive"))
      (node (ref "R4") (pin "1") (pinfunction "1_1") (pintype "passive"))
    )
    (net (code "60") (name "Net-(JPCAN-Pad1)") (class "Default")
      (node (ref "JPCAN") (pin "1") (pinfunction "1_1") (pintype "passive"))
      (node (ref "RCAN") (pin "2") (pinfunction "2_2") (pintype "bidirectional"))
    )
    (net (code "61") (name "Net-(LED_1-PadA)") (class "Default")
      (node (ref "LED_1") (pin "A") (pinfunction "A_A") (pintype "passive"))
      (node (ref "RL1") (pin "2") (pinfunction "2_2") (pintype "bidirectional"))
    )
    (net (code "62") (name "Net-(LED_2-PadA)") (class "Default")
      (node (ref "LED_2") (pin "A") (pinfunction "A_A") (pintype "passive"))
      (node (ref "RL2") (pin "2") (pinfunction "2_2") (pintype "bidirectional"))
    )
    (net (code "63") (name "Net-(LED_POW-PadA)") (class "Default")
      (node (ref "LED_POW") (pin "A") (pinfunction "A_A") (pintype "passive"))
      (node (ref "RLPOW") (pin "2") (pinfunction "2_2") (pintype "bidirectional"))
    )
    (net (code "64") (name "Net-(LED_RX-PadA)") (class "Default")
      (node (ref "LED_RX") (pin "A") (pinfunction "A_A") (pintype "passive"))
      (node (ref "RLRX") (pin "2") (pinfunction "2_2") (pintype "bidirectional"))
    )
    (net (code "65") (name "Net-(LED_TX-PadA)") (class "Default")
      (node (ref "LED_TX") (pin "A") (pinfunction "A_A") (pintype "passive"))
      (node (ref "RLTX") (pin "2") (pinfunction "2_2") (pintype "bidirectional"))
    )
    (net (code "66") (name "Net-(SWON-P)") (class "Default")
      (node (ref "JBAT") (pin "2") (pinfunction "2_2") (pintype "passive"))
      (node (ref "SWON") (pin "2") (pinfunction "P_2") (pintype "passive"))
    )
    (net (code "67") (name "Net-(UCAN-RS)") (class "Default")
      (node (ref "RS_CAN") (pin "2") (pinfunction "2_2") (pintype "bidirectional"))
      (node (ref "UCAN") (pin "8") (pinfunction "RS_8") (pintype "bidirectional"))
    )
    (net (code "68") (name "Net-(UDCDC-FB)") (class "Default")
      (node (ref "R1") (pin "1") (pinfunction "1_1") (pintype "passive"))
      (node (ref "R2") (pin "2") (pinfunction "2_2") (pintype "passive"))
      (node (ref "UDCDC") (pin "3") (pinfunction "FB_3") (pintype "bidirectional"))
    )
    (net (code "69") (name "Net-(UDCDC-SS)") (class "Default")
      (node (ref "C2") (pin "1") (pinfunction "1_1") (pintype "bidirectional"))
      (node (ref "UDCDC") (pin "5") (pinfunction "SS_5") (pintype "bidirectional"))
    )
    (net (code "70") (name "Net-(UDCDC-SW)") (class "Default")
      (node (ref "C3") (pin "1") (pinfunction "1_1") (pintype "passive"))
      (node (ref "C4") (pin "1") (pinfunction "1_1") (pintype "passive"))
      (node (ref "L1") (pin "2") (pinfunction "2_2") (pintype "passive"))
      (node (ref "UDCDC") (pin "1") (pinfunction "SW_1") (pintype "bidirectional"))
    )
    (net (code "71") (name "Net-(USUP-RESET)") (class "Default")
      (node (ref "R5") (pin "2") (pinfunction "2_2") (pintype "passive"))
      (node (ref "USUP") (pin "6") (pinfunction "RESET_6") (pintype "bidirectional"))
    )
    (net (code "72") (name "VBAT") (class "Default")
      (node (ref "C1") (pin "+") (pinfunction "+_+") (pintype "passive"))
      (node (ref "L1") (pin "1") (pinfunction "1_1") (pintype "passive"))
      (node (ref "R6") (pin "1") (pinfunction "1_1") (pintype "passive"))
      (node (ref "R7") (pin "1") (pinfunction "1_1") (pintype "passive"))
      (node (ref "SWON") (pin "1") (pinfunction "O_1") (pintype "passive"))
      (node (ref "UDCDC") (pin "6") (pinfunction "VIN_6") (pintype "bidirectional"))
      (node (ref "USUP") (pin "2") (pinfunction "~{RESIN}_2") (pintype "bidirectional"))
      (node (ref "USUP") (pin "7") (pinfunction "SENSE_7") (pintype "bidirectional"))
      (node (ref "USUP") (pin "8") (pinfunction "VCC_8") (pintype "bidirectional"))
    )
    (net (code "73") (name "unconnected-(JUSB-PadVBUS)") (class "Default")
      (node (ref "JUSB") (pin "VBUS") (pinfunction "VBUS_VBUS") (pintype "bidirectional"))
    )
    (net (code "74") (name "unconnected-(SWON-S-Pad3)") (class "Default")
      (node (ref "SWON") (pin "3") (pinfunction "S_3") (pintype "passive"))
    )
    (net (code "75") (name "unconnected-(UCAN-VREF-Pad5)") (class "Default")
      (node (ref "UCAN") (pin "5") (pinfunction "VREF_5") (pintype "bidirectional"))
    )
    (net (code "76") (name "unconnected-(UIMU-DRDY_G{slash}INT2_G-Pad5)") (class "Default")
      (node (ref "UIMU") (pin "5") (pinfunction "DRDY_G/INT2_G_5") (pintype "bidirectional"))
    )
    (net (code "77") (name "unconnected-(UIMU-INT1_A-Pad6)") (class "Default")
      (node (ref "UIMU") (pin "6") (pinfunction "INT1_A_6") (pintype "bidirectional"))
    )
    (net (code "78") (name "unconnected-(UIMU-INT1_G-Pad21)") (class "Default")
      (node (ref "UIMU") (pin "21") (pinfunction "INT1_G_21") (pintype "bidirectional"))
    )
    (net (code "79") (name "unconnected-(UIMU-INT2_A-Pad8)") (class "Default")
      (node (ref "UIMU") (pin "8") (pinfunction "INT2_A_8") (pintype "bidirectional"))
    )
    (net (code "80") (name "unconnected-(UPIC-RA4{slash}SOSCO{slash}T1CK-PadP$34)") (class "Default")
      (node (ref "UPIC") (pin "P$34") (pinfunction "RA4/SOSCO/T1CK_P$34") (pintype "bidirectional"))
    )
    (net (code "81") (name "unconnected-(UPIC-RA8{slash}TDO{slash}PMA8-PadP$32)") (class "Default")
      (node (ref "UPIC") (pin "P$32") (pinfunction "RA8/TDO/PMA8_P$32") (pintype "bidirectional"))
    )
    (net (code "82") (name "unconnected-(UPIC-RA9{slash}TDI{slash}PMA9-PadP$35)") (class "Default")
      (node (ref "UPIC") (pin "P$35") (pinfunction "RA9/TDI/PMA9_P$35") (pintype "bidirectional"))
    )
    (net (code "83") (name "unconnected-(UPIC-RB6*{slash}PGEC3{slash}ASCL1{slash}PMD6-PadP$42)") (class "Default")
      (node (ref "UPIC") (pin "P$42") (pinfunction "RB6*/PGEC3/ASCL1/PMD6_P$42") (pintype "bidirectional"))
    )
    (net (code "84") (name "unconnected-(UPIC-RB7*{slash}INT0{slash}PMD5-PadP$43)") (class "Default")
      (node (ref "UPIC") (pin "P$43") (pinfunction "RB7*/INT0/PMD5_P$43") (pintype "bidirectional"))
    )
    (net (code "85") (name "unconnected-(UPIC-RB8*{slash}SCL1{slash}PMD4-PadP$44)") (class "Default")
      (node (ref "UPIC") (pin "P$44") (pinfunction "RB8*/SCL1/PMD4_P$44") (pintype "bidirectional"))
    )
    (net (code "86") (name "unconnected-(UPIC-RB9*{slash}SDA1{slash}PMD3-PadP$1)") (class "Default")
      (node (ref "UPIC") (pin "P$1") (pinfunction "RB9*/SDA1/PMD3_P$1") (pintype "bidirectional"))
    )
    (net (code "87") (name "unconnected-(URF-GDO0{slash}ATEST-Pad6)") (class "Default")
      (node (ref "URF") (pin "6") (pinfunction "GDO0/ATEST_6") (pintype "bidirectional"))
    )
    (net (code "88") (name "unconnected-(URF-GDO2-Pad3)") (class "Default")
      (node (ref "URF") (pin "3") (pinfunction "GDO2_3") (pintype "bidirectional"))
    )
    (net (code "89") (name "unconnected-(UUSB-3V3OUT-Pad17)") (class "Default")
      (node (ref "UUSB") (pin "17") (pinfunction "3V3OUT_17") (pintype "output"))
    )
    (net (code "90") (name "unconnected-(UUSB-CTS-Pad11)") (class "Default")
      (node (ref "UUSB") (pin "11") (pinfunction "CTS_11") (pintype "bidirectional"))
    )
    (net (code "91") (name "unconnected-(UUSB-DTR-Pad2)") (class "Default")
      (node (ref "UUSB") (pin "2") (pinfunction "DTR_2") (pintype "bidirectional"))
    )
    (net (code "92") (name "unconnected-(UUSB-RTS-Pad3)") (class "Default")
      (node (ref "UUSB") (pin "3") (pinfunction "RTS_3") (pintype "bidirectional"))
    )
  )
)
